# CONNECTOR_A.net
KiCad netlist of a schematic drawn in Altium Designer
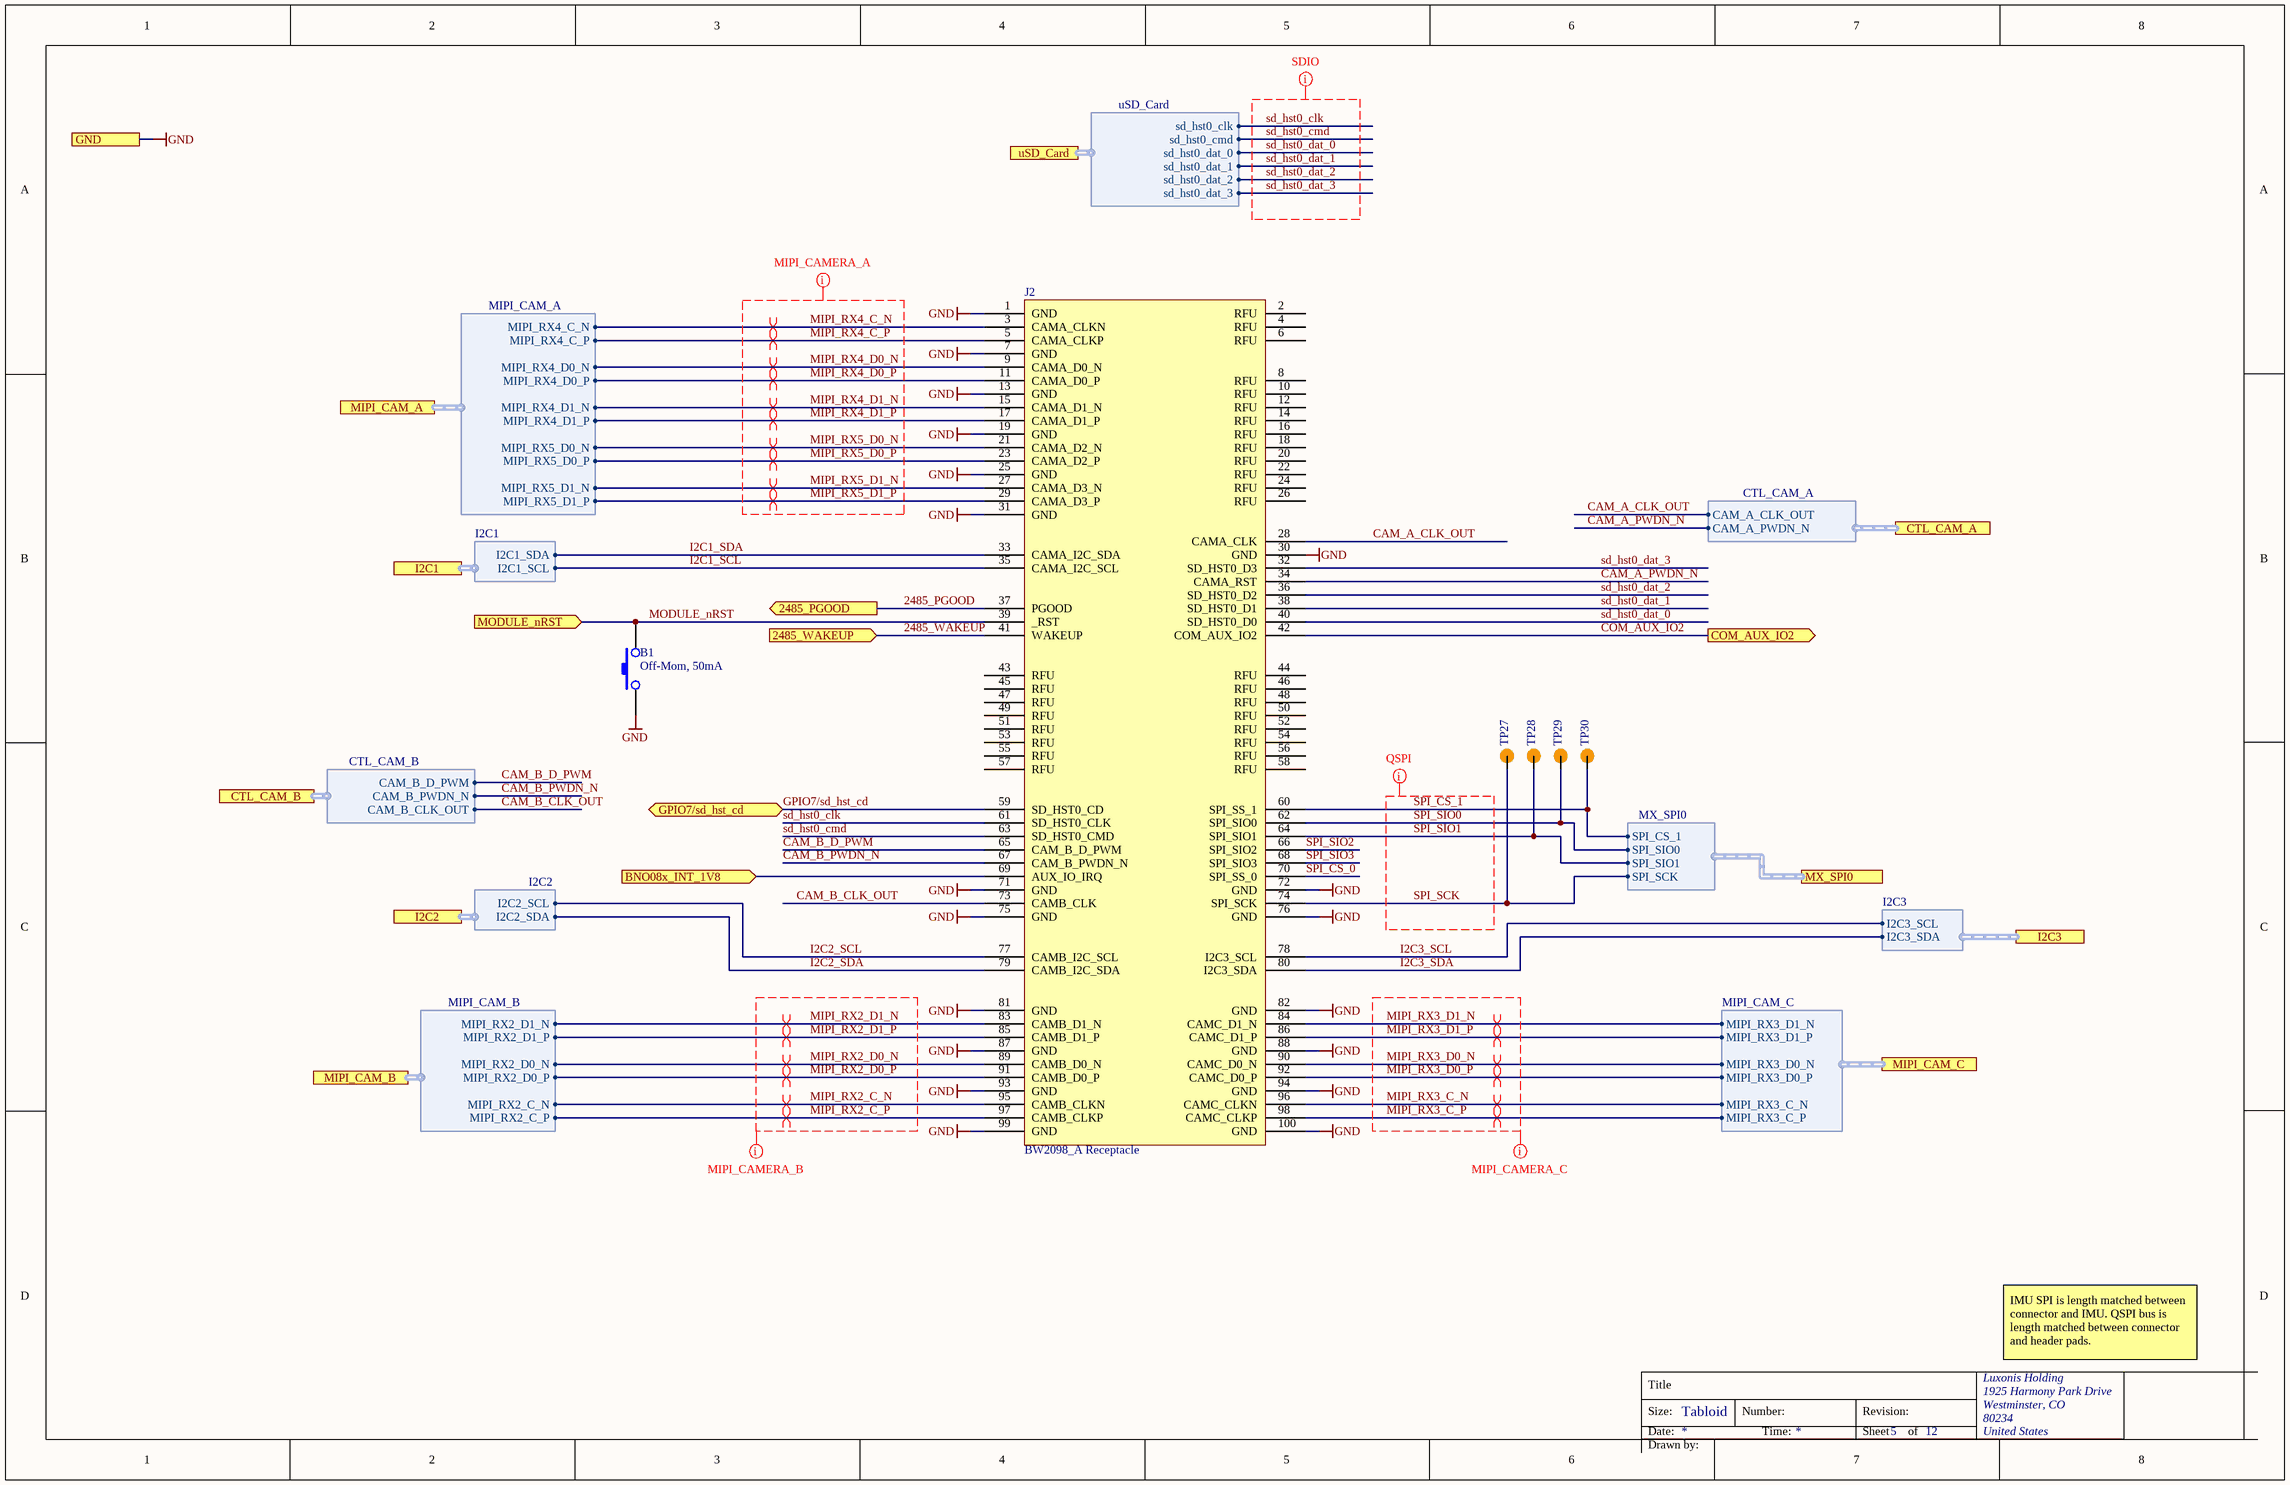
[diagram p0: CONNECTOR_A.SchDoc]

(export (version "E")
  (design (tool "Eeschema 10.0.6"))
  (components
    (comp (ref "B1")
      (value "Off-Mom, 50mA")
      (footprint "LuxonisMaster:DTSM-32N-V")
      (description "SWITCH TACTILE SMT 3.5mm * 6mm , brown 160gf")
      (libsource (lib "LuxonisMaster") (part "DTSM-32N-V"))
    )
    (comp (ref "J2")
      (value "BW2098_A Receptacle")
      (footprint "LuxonisMaster:DF40HC-3.0-100DS-0.4V_minpad")
      (description "CONN RCPT 100POS 0.4MM SMD GOLD BW2098_A Receptacle")
      (libsource (lib "BW2098POE") (part "DF40HC(3.0)-100DS-0.4V_BW2098_A"))
    )
    (comp (ref "TP27")
      (value "TP100_200_NS")
      (footprint "LuxonisMaster:TP100_200_NS")
      (libsource (lib "LuxonisMaster") (part "TEST_POINT"))
    )
    (comp (ref "TP28")
      (value "TP100_200_NS")
      (footprint "LuxonisMaster:TP100_200_NS")
      (libsource (lib "LuxonisMaster") (part "TEST_POINT"))
    )
    (comp (ref "TP29")
      (value "TP100_200_NS")
      (footprint "LuxonisMaster:TP100_200_NS")
      (libsource (lib "LuxonisMaster") (part "TEST_POINT"))
    )
    (comp (ref "TP30")
      (value "TP100_200_NS")
      (footprint "LuxonisMaster:TP100_200_NS")
      (libsource (lib "LuxonisMaster") (part "TEST_POINT"))
    )
  )
  (nets
    (net (code "11") (name "/2485_PGOOD") (class "Default")
      (node (ref "J2") (pin "37") (pinfunction "PGOOD_37") (pintype "passive"))
    )
    (net (code "12") (name "/2485_WAKEUP") (class "Default")
      (node (ref "J2") (pin "41") (pinfunction "WAKEUP_41") (pintype "passive"))
    )
    (net (code "13") (name "/BNO08x_INT_1V8") (class "Default")
      (node (ref "J2") (pin "69") (pinfunction "AUX_IO_IRQ_69") (pintype "passive"))
    )
    (net (code "14") (name "/CAM_A_CLK_OUT") (class "Default")
      (node (ref "J2") (pin "28") (pinfunction "CAMA_CLK_28") (pintype "passive"))
    )
    (net (code "15") (name "/CAM_A_PWDN_N") (class "Default")
      (node (ref "J2") (pin "34") (pinfunction "CAMA_RST_34") (pintype "passive"))
    )
    (net (code "16") (name "/CAM_B_CLK_OUT") (class "Default")
      (node (ref "J2") (pin "73") (pinfunction "CAMB_CLK_73") (pintype "passive"))
    )
    (net (code "17") (name "/CAM_B_D_PWM") (class "Default")
      (node (ref "J2") (pin "65") (pinfunction "CAM_B_D_PWM_65") (pintype "passive"))
    )
    (net (code "18") (name "/CAM_B_PWDN_N") (class "Default")
      (node (ref "J2") (pin "67") (pinfunction "CAM_B_PWDN_N_67") (pintype "passive"))
    )
    (net (code "19") (name "/COM_AUX_IO2") (class "Default")
      (node (ref "J2") (pin "42") (pinfunction "COM_AUX_IO2_42") (pintype "passive"))
    )
    (net (code "20") (name "/GPIO7{slash}sd_hst_cd") (class "Default")
      (node (ref "J2") (pin "59") (pinfunction "SD_HST0_CD_59") (pintype "passive"))
    )
    (net (code "21") (name "/I2C1_SCL") (class "Default")
      (node (ref "J2") (pin "35") (pinfunction "CAMA_I2C_SCL_35") (pintype "passive"))
    )
    (net (code "22") (name "/I2C1_SDA") (class "Default")
      (node (ref "J2") (pin "33") (pinfunction "CAMA_I2C_SDA_33") (pintype "passive"))
    )
    (net (code "23") (name "/I2C2_SCL") (class "Default")
      (node (ref "J2") (pin "77") (pinfunction "CAMB_I2C_SCL_77") (pintype "passive"))
    )
    (net (code "24") (name "/I2C2_SDA") (class "Default")
      (node (ref "J2") (pin "79") (pinfunction "CAMB_I2C_SDA_79") (pintype "passive"))
    )
    (net (code "25") (name "/I2C3_SCL") (class "Default")
      (node (ref "J2") (pin "78") (pinfunction "I2C3_SCL_78") (pintype "passive"))
    )
    (net (code "26") (name "/I2C3_SDA") (class "Default")
      (node (ref "J2") (pin "80") (pinfunction "I2C3_SDA_80") (pintype "passive"))
    )
    (net (code "27") (name "/MIPI_RX2_C_N") (class "Default")
      (node (ref "J2") (pin "95") (pinfunction "CAMB_CLKN_95") (pintype "passive"))
    )
    (net (code "28") (name "/MIPI_RX2_C_P") (class "Default")
      (node (ref "J2") (pin "97") (pinfunction "CAMB_CLKP_97") (pintype "passive"))
    )
    (net (code "29") (name "/MIPI_RX2_D0_N") (class "Default")
      (node (ref "J2") (pin "89") (pinfunction "CAMB_D0_N_89") (pintype "passive"))
    )
    (net (code "30") (name "/MIPI_RX2_D0_P") (class "Default")
      (node (ref "J2") (pin "91") (pinfunction "CAMB_D0_P_91") (pintype "passive"))
    )
    (net (code "31") (name "/MIPI_RX2_D1_N") (class "Default")
      (node (ref "J2") (pin "83") (pinfunction "CAMB_D1_N_83") (pintype "passive"))
    )
    (net (code "32") (name "/MIPI_RX2_D1_P") (class "Default")
      (node (ref "J2") (pin "85") (pinfunction "CAMB_D1_P_85") (pintype "passive"))
    )
    (net (code "33") (name "/MIPI_RX3_C_N") (class "Default")
      (node (ref "J2") (pin "96") (pinfunction "CAMC_CLKN_96") (pintype "passive"))
    )
    (net (code "34") (name "/MIPI_RX3_C_P") (class "Default")
      (node (ref "J2") (pin "98") (pinfunction "CAMC_CLKP_98") (pintype "passive"))
    )
    (net (code "35") (name "/MIPI_RX3_D0_N") (class "Default")
      (node (ref "J2") (pin "90") (pinfunction "CAMC_D0_N_90") (pintype "passive"))
    )
    (net (code "36") (name "/MIPI_RX3_D0_P") (class "Default")
      (node (ref "J2") (pin "92") (pinfunction "CAMC_D0_P_92") (pintype "passive"))
    )
    (net (code "37") (name "/MIPI_RX3_D1_N") (class "Default")
      (node (ref "J2") (pin "84") (pinfunction "CAMC_D1_N_84") (pintype "passive"))
    )
    (net (code "38") (name "/MIPI_RX3_D1_P") (class "Default")
      (node (ref "J2") (pin "86") (pinfunction "CAMC_D1_P_86") (pintype "passive"))
    )
    (net (code "39") (name "/MIPI_RX4_C_N") (class "Default")
      (node (ref "J2") (pin "3") (pinfunction "CAMA_CLKN_3") (pintype "passive"))
    )
    (net (code "40") (name "/MIPI_RX4_C_P") (class "Default")
      (node (ref "J2") (pin "5") (pinfunction "CAMA_CLKP_5") (pintype "passive"))
    )
    (net (code "41") (name "/MIPI_RX4_D0_N") (class "Default")
      (node (ref "J2") (pin "9") (pinfunction "CAMA_D0_N_9") (pintype "passive"))
    )
    (net (code "42") (name "/MIPI_RX4_D0_P") (class "Default")
      (node (ref "J2") (pin "11") (pinfunction "CAMA_D0_P_11") (pintype "passive"))
    )
    (net (code "43") (name "/MIPI_RX4_D1_N") (class "Default")
      (node (ref "J2") (pin "15") (pinfunction "CAMA_D1_N_15") (pintype "passive"))
    )
    (net (code "44") (name "/MIPI_RX4_D1_P") (class "Default")
      (node (ref "J2") (pin "17") (pinfunction "CAMA_D1_P_17") (pintype "passive"))
    )
    (net (code "45") (name "/MIPI_RX5_D0_N") (class "Default")
      (node (ref "J2") (pin "21") (pinfunction "CAMA_D2_N_21") (pintype "passive"))
    )
    (net (code "46") (name "/MIPI_RX5_D0_P") (class "Default")
      (node (ref "J2") (pin "23") (pinfunction "CAMA_D2_P_23") (pintype "passive"))
    )
    (net (code "47") (name "/MIPI_RX5_D1_N") (class "Default")
      (node (ref "J2") (pin "27") (pinfunction "CAMA_D3_N_27") (pintype "passive"))
    )
    (net (code "48") (name "/MIPI_RX5_D1_P") (class "Default")
      (node (ref "J2") (pin "29") (pinfunction "CAMA_D3_P_29") (pintype "passive"))
    )
    (net (code "49") (name "/MODULE_nRST") (class "Default")
      (node (ref "B1") (pin "2") (pinfunction "2_2") (pintype "passive"))
      (node (ref "J2") (pin "39") (pinfunction "_RST_39") (pintype "passive"))
    )
    (net (code "50") (name "/SPI_CS_0") (class "Default")
      (node (ref "J2") (pin "70") (pinfunction "SPI_SS_0_70") (pintype "passive"))
    )
    (net (code "51") (name "/SPI_CS_1") (class "Default")
      (node (ref "J2") (pin "60") (pinfunction "SPI_SS_1_60") (pintype "passive"))
      (node (ref "TP30") (pin "1") (pintype "passive"))
    )
    (net (code "52") (name "/SPI_SCK") (class "Default")
      (node (ref "J2") (pin "74") (pinfunction "SPI_SCK_74") (pintype "passive"))
      (node (ref "TP27") (pin "1") (pintype "passive"))
    )
    (net (code "53") (name "/SPI_SIO0") (class "Default")
      (node (ref "J2") (pin "62") (pinfunction "SPI_SIO0_62") (pintype "passive"))
      (node (ref "TP29") (pin "1") (pintype "passive"))
    )
    (net (code "54") (name "/SPI_SIO1") (class "Default")
      (node (ref "J2") (pin "64") (pinfunction "SPI_SIO1_64") (pintype "passive"))
      (node (ref "TP28") (pin "1") (pintype "passive"))
    )
    (net (code "55") (name "/SPI_SIO2") (class "Default")
      (node (ref "J2") (pin "66") (pinfunction "SPI_SIO2_66") (pintype "passive"))
    )
    (net (code "56") (name "/SPI_SIO3") (class "Default")
      (node (ref "J2") (pin "68") (pinfunction "SPI_SIO3_68") (pintype "passive"))
    )
    (net (code "57") (name "/sd_hst0_clk") (class "Default")
      (node (ref "J2") (pin "61") (pinfunction "SD_HST0_CLK_61") (pintype "passive"))
    )
    (net (code "58") (name "/sd_hst0_cmd") (class "Default")
      (node (ref "J2") (pin "63") (pinfunction "SD_HST0_CMD_63") (pintype "passive"))
    )
    (net (code "59") (name "/sd_hst0_dat_0") (class "Default")
      (node (ref "J2") (pin "40") (pinfunction "SD_HST0_D0_40") (pintype "passive"))
    )
    (net (code "60") (name "/sd_hst0_dat_1") (class "Default")
      (node (ref "J2") (pin "38") (pinfunction "SD_HST0_D1_38") (pintype "passive"))
    )
    (net (code "61") (name "/sd_hst0_dat_2") (class "Default")
      (node (ref "J2") (pin "36") (pinfunction "SD_HST0_D2_36") (pintype "passive"))
    )
    (net (code "62") (name "/sd_hst0_dat_3") (class "Default")
      (node (ref "J2") (pin "32") (pinfunction "SD_HST0_D3_32") (pintype "passive"))
    )
    (net (code "73") (name "GND") (class "Default")
      (node (ref "B1") (pin "1") (pinfunction "1_1") (pintype "passive"))
      (node (ref "J2") (pin "1") (pinfunction "GND_1") (pintype "passive"))
      (node (ref "J2") (pin "100") (pinfunction "GND_100") (pintype "passive"))
      (node (ref "J2") (pin "13") (pinfunction "GND_13") (pintype "passive"))
      (node (ref "J2") (pin "19") (pinfunction "GND_19") (pintype "passive"))
      (node (ref "J2") (pin "25") (pinfunction "GND_25") (pintype "passive"))
      (node (ref "J2") (pin "30") (pinfunction "GND_30") (pintype "passive"))
      (node (ref "J2") (pin "31") (pinfunction "GND_31") (pintype "passive"))
      (node (ref "J2") (pin "7") (pinfunction "GND_7") (pintype "passive"))
      (node (ref "J2") (pin "71") (pinfunction "GND_71") (pintype "passive"))
      (node (ref "J2") (pin "72") (pinfunction "GND_72") (pintype "passive"))
      (node (ref "J2") (pin "75") (pinfunction "GND_75") (pintype "passive"))
      (node (ref "J2") (pin "76") (pinfunction "GND_76") (pintype "passive"))
      (node (ref "J2") (pin "81") (pinfunction "GND_81") (pintype "passive"))
      (node (ref "J2") (pin "82") (pinfunction "GND_82") (pintype "passive"))
      (node (ref "J2") (pin "87") (pinfunction "GND_87") (pintype "passive"))
      (node (ref "J2") (pin "88") (pinfunction "GND_88") (pintype "passive"))
      (node (ref "J2") (pin "93") (pinfunction "GND_93") (pintype "passive"))
      (node (ref "J2") (pin "94") (pinfunction "GND_94") (pintype "passive"))
      (node (ref "J2") (pin "99") (pinfunction "GND_99") (pintype "passive"))
    )
    (net (code "74") (name "unconnected-(J2-RFU-Pad2)") (class "Default")
      (node (ref "J2") (pin "2") (pinfunction "RFU_2") (pintype "passive"))
    )
    (net (code "75") (name "unconnected-(J2-RFU-Pad4)") (class "Default")
      (node (ref "J2") (pin "4") (pinfunction "RFU_4") (pintype "passive"))
    )
    (net (code "76") (name "unconnected-(J2-RFU-Pad6)") (class "Default")
      (node (ref "J2") (pin "6") (pinfunction "RFU_6") (pintype "passive"))
    )
    (net (code "77") (name "unconnected-(J2-RFU-Pad8)") (class "Default")
      (node (ref "J2") (pin "8") (pinfunction "RFU_8") (pintype "passive"))
    )
    (net (code "78") (name "unconnected-(J2-RFU-Pad10)") (class "Default")
      (node (ref "J2") (pin "10") (pinfunction "RFU_10") (pintype "passive"))
    )
    (net (code "79") (name "unconnected-(J2-RFU-Pad12)") (class "Default")
      (node (ref "J2") (pin "12") (pinfunction "RFU_12") (pintype "passive"))
    )
    (net (code "80") (name "unconnected-(J2-RFU-Pad14)") (class "Default")
      (node (ref "J2") (pin "14") (pinfunction "RFU_14") (pintype "passive"))
    )
    (net (code "81") (name "unconnected-(J2-RFU-Pad16)") (class "Default")
      (node (ref "J2") (pin "16") (pinfunction "RFU_16") (pintype "passive"))
    )
    (net (code "82") (name "unconnected-(J2-RFU-Pad18)") (class "Default")
      (node (ref "J2") (pin "18") (pinfunction "RFU_18") (pintype "passive"))
    )
    (net (code "83") (name "unconnected-(J2-RFU-Pad20)") (class "Default")
      (node (ref "J2") (pin "20") (pinfunction "RFU_20") (pintype "passive"))
    )
    (net (code "84") (name "unconnected-(J2-RFU-Pad22)") (class "Default")
      (node (ref "J2") (pin "22") (pinfunction "RFU_22") (pintype "passive"))
    )
    (net (code "85") (name "unconnected-(J2-RFU-Pad24)") (class "Default")
      (node (ref "J2") (pin "24") (pinfunction "RFU_24") (pintype "passive"))
    )
    (net (code "86") (name "unconnected-(J2-RFU-Pad26)") (class "Default")
      (node (ref "J2") (pin "26") (pinfunction "RFU_26") (pintype "passive"))
    )
    (net (code "87") (name "unconnected-(J2-RFU-Pad43)") (class "Default")
      (node (ref "J2") (pin "43") (pinfunction "RFU_43") (pintype "passive"))
    )
    (net (code "88") (name "unconnected-(J2-RFU-Pad44)") (class "Default")
      (node (ref "J2") (pin "44") (pinfunction "RFU_44") (pintype "passive"))
    )
    (net (code "89") (name "unconnected-(J2-RFU-Pad45)") (class "Default")
      (node (ref "J2") (pin "45") (pinfunction "RFU_45") (pintype "passive"))
    )
    (net (code "90") (name "unconnected-(J2-RFU-Pad46)") (class "Default")
      (node (ref "J2") (pin "46") (pinfunction "RFU_46") (pintype "passive"))
    )
    (net (code "91") (name "unconnected-(J2-RFU-Pad47)") (class "Default")
      (node (ref "J2") (pin "47") (pinfunction "RFU_47") (pintype "passive"))
    )
    (net (code "92") (name "unconnected-(J2-RFU-Pad48)") (class "Default")
      (node (ref "J2") (pin "48") (pinfunction "RFU_48") (pintype "passive"))
    )
    (net (code "93") (name "unconnected-(J2-RFU-Pad49)") (class "Default")
      (node (ref "J2") (pin "49") (pinfunction "RFU_49") (pintype "passive"))
    )
    (net (code "94") (name "unconnected-(J2-RFU-Pad50)") (class "Default")
      (node (ref "J2") (pin "50") (pinfunction "RFU_50") (pintype "passive"))
    )
    (net (code "95") (name "unconnected-(J2-RFU-Pad51)") (class "Default")
      (node (ref "J2") (pin "51") (pinfunction "RFU_51") (pintype "passive"))
    )
    (net (code "96") (name "unconnected-(J2-RFU-Pad52)") (class "Default")
      (node (ref "J2") (pin "52") (pinfunction "RFU_52") (pintype "passive"))
    )
    (net (code "97") (name "unconnected-(J2-RFU-Pad53)") (class "Default")
      (node (ref "J2") (pin "53") (pinfunction "RFU_53") (pintype "passive"))
    )
    (net (code "98") (name "unconnected-(J2-RFU-Pad54)") (class "Default")
      (node (ref "J2") (pin "54") (pinfunction "RFU_54") (pintype "passive"))
    )
    (net (code "99") (name "unconnected-(J2-RFU-Pad55)") (class "Default")
      (node (ref "J2") (pin "55") (pinfunction "RFU_55") (pintype "passive"))
    )
    (net (code "100") (name "unconnected-(J2-RFU-Pad56)") (class "Default")
      (node (ref "J2") (pin "56") (pinfunction "RFU_56") (pintype "passive"))
    )
    (net (code "101") (name "unconnected-(J2-RFU-Pad57)") (class "Default")
      (node (ref "J2") (pin "57") (pinfunction "RFU_57") (pintype "passive"))
    )
    (net (code "102") (name "unconnected-(J2-RFU-Pad58)") (class "Default")
      (node (ref "J2") (pin "58") (pinfunction "RFU_58") (pintype "passive"))
    )
  )
)
